# db9nes.net
KiCad netlist of a schematic drawn in EAGLE
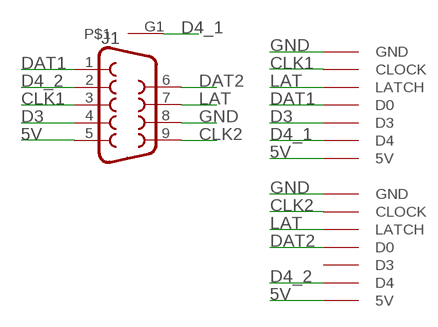
[diagram p0: schematic, sheet 1]

(export (version "E")
  (design (tool "Eeschema 10.0.6"))
  (components
    (comp (ref "J1")
      (value "DB9FEMALE")
      (footprint "eagle-import:DB9")
      (libsource (lib "eagle-import") (part "DB9FEMALE"))
    )
    (comp (ref "U$1")
      (value "NESCONNNO_TABS")
      (footprint "eagle-import:NESCONN_NO_TABS")
      (libsource (lib "eagle-import") (part "NESCONNNO_TABS"))
    )
    (comp (ref "U$2")
      (value "NESCONNNO_TABS")
      (footprint "eagle-import:NESCONN_NO_TABS")
      (libsource (lib "eagle-import") (part "NESCONNNO_TABS"))
    )
  )
  (nets
    (net (code "1") (name "/5V") (class "Default")
      (node (ref "J1") (pin "5") (pinfunction "5_5") (pintype "passive"))
      (node (ref "U$1") (pin "5V") (pinfunction "5V_5V") (pintype "power_in"))
      (node (ref "U$2") (pin "5V") (pinfunction "5V_5V") (pintype "power_in"))
    )
    (net (code "2") (name "/CLK1") (class "Default")
      (node (ref "J1") (pin "3") (pinfunction "3_3") (pintype "passive"))
      (node (ref "U$2") (pin "CLOCK") (pinfunction "CLOCK_CLOCK") (pintype "input"))
    )
    (net (code "3") (name "/CLK2") (class "Default")
      (node (ref "J1") (pin "9") (pinfunction "9_9") (pintype "passive"))
      (node (ref "U$1") (pin "CLOCK") (pinfunction "CLOCK_CLOCK") (pintype "input"))
    )
    (net (code "4") (name "/D3") (class "Default")
      (node (ref "J1") (pin "4") (pinfunction "4_4") (pintype "passive"))
      (node (ref "U$2") (pin "D3") (pinfunction "D3_D3") (pintype "bidirectional"))
    )
    (net (code "5") (name "/D4_1") (class "Default")
      (node (ref "J1") (pin "G1") (pinfunction "P$1_G1") (pintype "bidirectional"))
      (node (ref "U$2") (pin "D4") (pinfunction "D4_D4") (pintype "bidirectional"))
    )
    (net (code "6") (name "/D4_2") (class "Default")
      (node (ref "J1") (pin "2") (pinfunction "2_2") (pintype "passive"))
      (node (ref "U$1") (pin "D4") (pinfunction "D4_D4") (pintype "bidirectional"))
    )
    (net (code "7") (name "/DAT1") (class "Default")
      (node (ref "J1") (pin "1") (pinfunction "1_1") (pintype "passive"))
      (node (ref "U$2") (pin "D0") (pinfunction "D0_D0") (pintype "bidirectional"))
    )
    (net (code "8") (name "/DAT2") (class "Default")
      (node (ref "J1") (pin "6") (pinfunction "6_6") (pintype "passive"))
      (node (ref "U$1") (pin "D0") (pinfunction "D0_D0") (pintype "bidirectional"))
    )
    (net (code "9") (name "/GND") (class "Default")
      (node (ref "J1") (pin "8") (pinfunction "8_8") (pintype "passive"))
      (node (ref "U$1") (pin "GND") (pinfunction "GND_GND") (pintype "input"))
      (node (ref "U$2") (pin "GND") (pinfunction "GND_GND") (pintype "input"))
    )
    (net (code "10") (name "/LAT") (class "Default")
      (node (ref "J1") (pin "7") (pinfunction "7_7") (pintype "passive"))
      (node (ref "U$1") (pin "LATCH") (pinfunction "LATCH_LATCH") (pintype "input"))
      (node (ref "U$2") (pin "LATCH") (pinfunction "LATCH_LATCH") (pintype "input"))
    )
    (net (code "11") (name "unconnected-(U$1-PadD3)") (class "Default")
      (node (ref "U$1") (pin "D3") (pinfunction "D3_D3") (pintype "bidirectional"))
    )
  )
)
